# TopSheet.net
KiCad netlist of a schematic drawn in Altium Designer
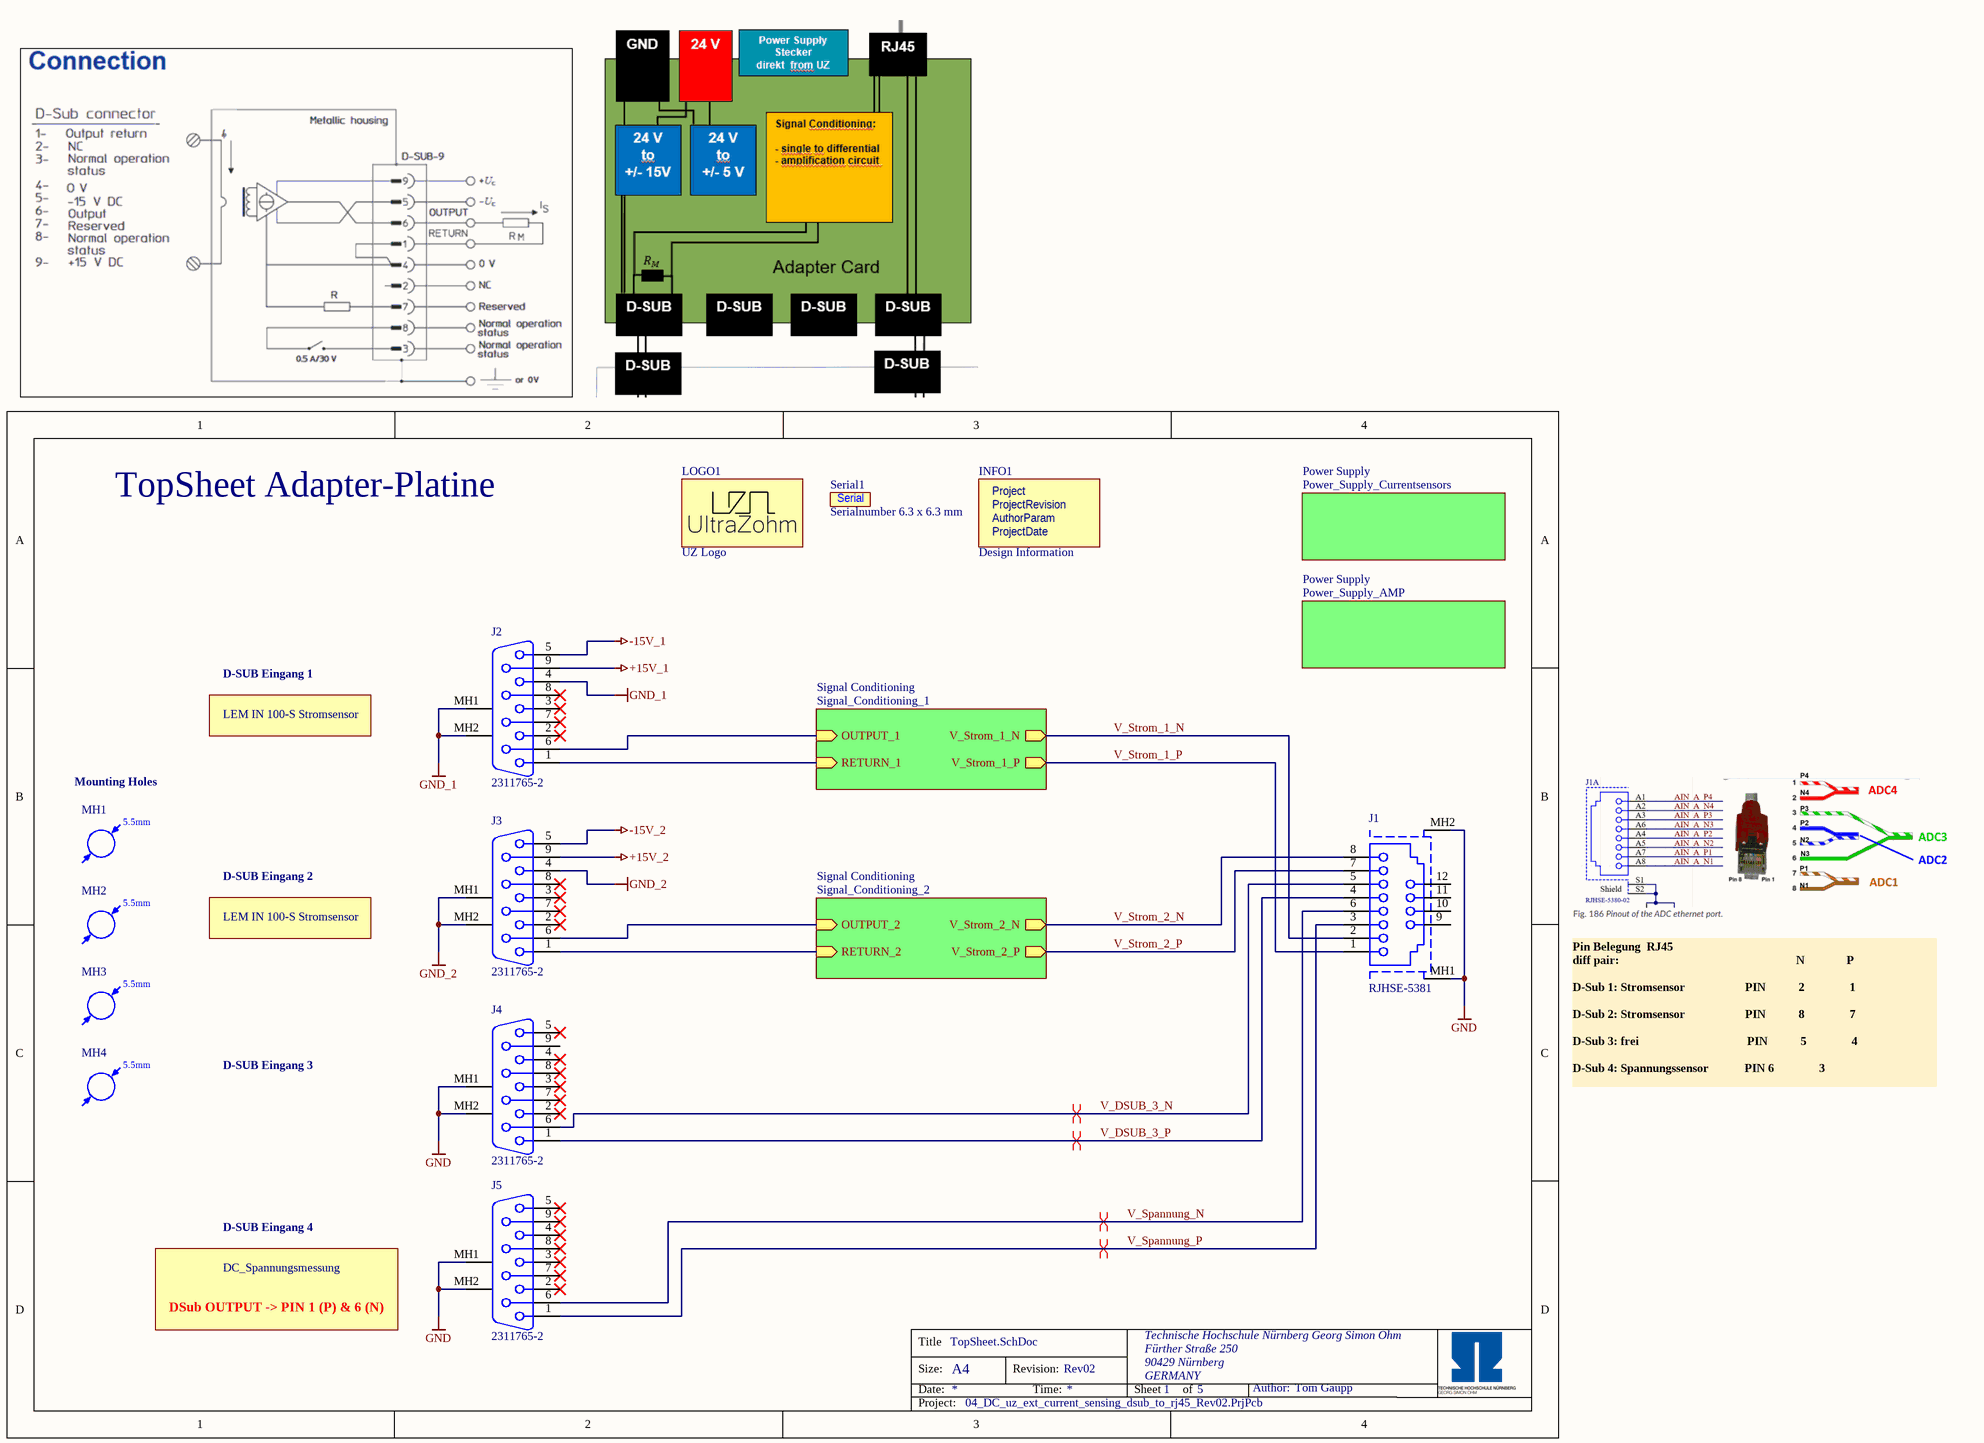
[diagram p0: TopSheet.SchDoc]

(export (version "E")
  (design (tool "Eeschema 10.0.6"))
  (components
    (comp (ref "INFO1")
      (value "Design Information")
      (footprint "Design_info")
      (description "Design InformationS")
      (fields (field (name "MANUFACTURER") "UltraZohm") (field (name "CREATED FROM") "MGremer"))
      (libsource (lib "user") (part "Design_info"))
    )
    (comp (ref "J1")
      (value "RJHSE-5381")
      (footprint "eigene_lib_alt:RJHSE-5381")
      (description "Connector Ethernet R/A RJ45 SHIELDED 8 CONT Y/G LEDS")
      (libsource (lib "eigene_lib_alt") (part "RJHSE-5381"))
    )
    (comp (ref "J2")
      (value "2311765-2")
      (footprint "eigene_lib_alt:23117652")
      (description "Connector D-Sub 9 Pin Female")
      (fields (field (name "MOUSER PART NUMBER") "571-2311765-2"))
      (libsource (lib "eigene_lib_alt") (part "2311765-2"))
    )
    (comp (ref "J3")
      (value "2311765-2")
      (footprint "eigene_lib_alt:23117652")
      (description "Connector D-Sub 9 Pin Female")
      (fields (field (name "MOUSER PART NUMBER") "571-2311765-2"))
      (libsource (lib "eigene_lib_alt") (part "2311765-2"))
    )
    (comp (ref "J4")
      (value "2311765-2")
      (footprint "eigene_lib_alt:23117652")
      (description "Connector D-Sub 9 Pin Female")
      (fields (field (name "MOUSER PART NUMBER") "571-2311765-2"))
      (libsource (lib "eigene_lib_alt") (part "2311765-2"))
    )
    (comp (ref "J5")
      (value "2311765-2")
      (footprint "eigene_lib_alt:23117652")
      (description "Connector D-Sub 9 Pin Female")
      (fields (field (name "MOUSER PART NUMBER") "571-2311765-2"))
      (libsource (lib "eigene_lib_alt") (part "2311765-2"))
    )
    (comp (ref "LOGO1")
      (value "UZ Logo")
      (footprint "UZ_Logo_small")
      (fields
        (field (name "MANUFACTURER PART NUMBER") "Logo small")
        (field (name "MANUFACTURER") "UltraZohm")
        (field (name "CREATED") "Jan2021_Liegmann")
        (field (name "CREATED FROM") "MGremer")
      )
      (libsource (lib "user") (part "UZ Logo"))
    )
    (comp (ref "MH1")
      (value "Mounting_Hole_M5")
      (footprint "Mounting_Hole_M5:Mounting Hole (M5)")
      (description "Mounting Hole")
      (libsource (lib "Mounting_Hole_M5") (part "Mounting_Hole_M5"))
    )
    (comp (ref "MH2")
      (value "Mounting_Hole_M5")
      (footprint "Mounting_Hole_M5:Mounting Hole (M5)")
      (description "Mounting Hole")
      (libsource (lib "Mounting_Hole_M5") (part "Mounting_Hole_M5"))
    )
    (comp (ref "MH3")
      (value "Mounting_Hole_M5")
      (footprint "Mounting_Hole_M5:Mounting Hole (M5)")
      (description "Mounting Hole")
      (libsource (lib "Mounting_Hole_M5") (part "Mounting_Hole_M5"))
    )
    (comp (ref "MH4")
      (value "Mounting_Hole_M5")
      (footprint "Mounting_Hole_M5:Mounting Hole (M5)")
      (description "Mounting Hole")
      (libsource (lib "Mounting_Hole_M5") (part "Mounting_Hole_M5"))
    )
    (comp (ref "Serial1")
      (value "Serialnumber 6.3 x 6.3 mm")
      (footprint "SERIAL_6.3X6.3MM")
      (description "Serial Number")
      (fields
        (field (name "MANUFACTURER") "UltraZohm")
        (field (name "CREATED") "2018_09_18_AGeiger")
        (field (name "CREATED FROM") "MGremer")
      )
      (libsource (lib "user") (part "SerialNumber"))
    )
  )
  (nets
    (net (code "1") (name "+15V_1") (class "Default")
      (node (ref "J2") (pin "9") (pinfunction "9_9") (pintype "passive"))
    )
    (net (code "2") (name "+15V_2") (class "Default")
      (node (ref "J3") (pin "9") (pinfunction "9_9") (pintype "passive"))
    )
    (net (code "3") (name "-15V_1") (class "Default")
      (node (ref "J2") (pin "5") (pinfunction "5_5") (pintype "passive"))
    )
    (net (code "4") (name "-15V_2") (class "Default")
      (node (ref "J3") (pin "5") (pinfunction "5_5") (pintype "passive"))
    )
    (net (code "5") (name "/OUTPUT_1") (class "Default")
      (node (ref "J2") (pin "6") (pinfunction "6_6") (pintype "passive"))
    )
    (net (code "6") (name "/OUTPUT_2") (class "Default")
      (node (ref "J3") (pin "6") (pinfunction "6_6") (pintype "passive"))
    )
    (net (code "7") (name "/RETURN_1") (class "Default")
      (node (ref "J2") (pin "1") (pinfunction "1_1") (pintype "passive"))
    )
    (net (code "8") (name "/RETURN_2") (class "Default")
      (node (ref "J3") (pin "1") (pinfunction "1_1") (pintype "passive"))
    )
    (net (code "9") (name "/V_DSUB_3_N") (class "Default")
      (node (ref "J1") (pin "5") (pinfunction "5_5") (pintype "passive"))
      (node (ref "J4") (pin "6") (pinfunction "6_6") (pintype "passive"))
    )
    (net (code "10") (name "/V_DSUB_3_P") (class "Default")
      (node (ref "J1") (pin "4") (pinfunction "4_4") (pintype "passive"))
      (node (ref "J4") (pin "1") (pinfunction "1_1") (pintype "passive"))
    )
    (net (code "11") (name "/V_Spannung_N") (class "Default")
      (node (ref "J1") (pin "6") (pinfunction "6_6") (pintype "passive"))
      (node (ref "J5") (pin "6") (pinfunction "6_6") (pintype "passive"))
    )
    (net (code "12") (name "/V_Spannung_P") (class "Default")
      (node (ref "J1") (pin "3") (pinfunction "3_3") (pintype "passive"))
      (node (ref "J5") (pin "1") (pinfunction "1_1") (pintype "passive"))
    )
    (net (code "13") (name "/V_Strom_1_N") (class "Default")
      (node (ref "J1") (pin "2") (pinfunction "2_2") (pintype "passive"))
    )
    (net (code "14") (name "/V_Strom_1_P") (class "Default")
      (node (ref "J1") (pin "1") (pinfunction "1_1") (pintype "passive"))
    )
    (net (code "15") (name "/V_Strom_2_N") (class "Default")
      (node (ref "J1") (pin "8") (pinfunction "8_8") (pintype "passive"))
    )
    (net (code "16") (name "/V_Strom_2_P") (class "Default")
      (node (ref "J1") (pin "7") (pinfunction "7_7") (pintype "passive"))
    )
    (net (code "17") (name "GND") (class "Default")
      (node (ref "J1") (pin "MH1") (pinfunction "Shell_MH1") (pintype "passive"))
      (node (ref "J1") (pin "MH2") (pinfunction "Shell_MH2") (pintype "passive"))
      (node (ref "J4") (pin "MH1") (pinfunction "MH1_MH1") (pintype "passive"))
      (node (ref "J4") (pin "MH2") (pinfunction "MH2_MH2") (pintype "passive"))
      (node (ref "J5") (pin "MH1") (pinfunction "MH1_MH1") (pintype "passive"))
      (node (ref "J5") (pin "MH2") (pinfunction "MH2_MH2") (pintype "passive"))
    )
    (net (code "18") (name "GND_1") (class "Default")
      (node (ref "J2") (pin "4") (pinfunction "4_4") (pintype "passive"))
      (node (ref "J2") (pin "MH1") (pinfunction "MH1_MH1") (pintype "passive"))
      (node (ref "J2") (pin "MH2") (pinfunction "MH2_MH2") (pintype "passive"))
    )
    (net (code "19") (name "GND_2") (class "Default")
      (node (ref "J3") (pin "4") (pinfunction "4_4") (pintype "passive"))
      (node (ref "J3") (pin "MH1") (pinfunction "MH1_MH1") (pintype "passive"))
      (node (ref "J3") (pin "MH2") (pinfunction "MH2_MH2") (pintype "passive"))
    )
    (net (code "20") (name "unconnected-(J1-8-Pad9)") (class "Default")
      (node (ref "J1") (pin "9") (pinfunction "8_9") (pintype "passive"))
    )
    (net (code "21") (name "unconnected-(J1-8-Pad10)") (class "Default")
      (node (ref "J1") (pin "10") (pinfunction "8_10") (pintype "passive"))
    )
    (net (code "22") (name "unconnected-(J1-8-Pad11)") (class "Default")
      (node (ref "J1") (pin "11") (pinfunction "8_11") (pintype "passive"))
    )
    (net (code "23") (name "unconnected-(J1-8-Pad12)") (class "Default")
      (node (ref "J1") (pin "12") (pinfunction "8_12") (pintype "passive"))
    )
    (net (code "24") (name "unconnected-(J2-Pad2)") (class "Default")
      (node (ref "J2") (pin "2") (pinfunction "2_2") (pintype "passive+no_connect"))
    )
    (net (code "25") (name "unconnected-(J2-Pad3)") (class "Default")
      (node (ref "J2") (pin "3") (pinfunction "3_3") (pintype "passive+no_connect"))
    )
    (net (code "26") (name "unconnected-(J2-Pad7)") (class "Default")
      (node (ref "J2") (pin "7") (pinfunction "7_7") (pintype "passive+no_connect"))
    )
    (net (code "27") (name "unconnected-(J2-Pad8)") (class "Default")
      (node (ref "J2") (pin "8") (pinfunction "8_8") (pintype "passive+no_connect"))
    )
    (net (code "28") (name "unconnected-(J3-Pad2)") (class "Default")
      (node (ref "J3") (pin "2") (pinfunction "2_2") (pintype "passive+no_connect"))
    )
    (net (code "29") (name "unconnected-(J3-Pad3)") (class "Default")
      (node (ref "J3") (pin "3") (pinfunction "3_3") (pintype "passive+no_connect"))
    )
    (net (code "30") (name "unconnected-(J3-Pad7)") (class "Default")
      (node (ref "J3") (pin "7") (pinfunction "7_7") (pintype "passive+no_connect"))
    )
    (net (code "31") (name "unconnected-(J3-Pad8)") (class "Default")
      (node (ref "J3") (pin "8") (pinfunction "8_8") (pintype "passive+no_connect"))
    )
    (net (code "32") (name "unconnected-(J4-Pad2)") (class "Default")
      (node (ref "J4") (pin "2") (pinfunction "2_2") (pintype "passive+no_connect"))
    )
    (net (code "33") (name "unconnected-(J4-Pad3)") (class "Default")
      (node (ref "J4") (pin "3") (pinfunction "3_3") (pintype "passive+no_connect"))
    )
    (net (code "34") (name "unconnected-(J4-Pad4)") (class "Default")
      (node (ref "J4") (pin "4") (pinfunction "4_4") (pintype "passive+no_connect"))
    )
    (net (code "35") (name "unconnected-(J4-Pad5)") (class "Default")
      (node (ref "J4") (pin "5") (pinfunction "5_5") (pintype "passive+no_connect"))
    )
    (net (code "36") (name "unconnected-(J4-Pad7)") (class "Default")
      (node (ref "J4") (pin "7") (pinfunction "7_7") (pintype "passive+no_connect"))
    )
    (net (code "37") (name "unconnected-(J4-Pad8)") (class "Default")
      (node (ref "J4") (pin "8") (pinfunction "8_8") (pintype "passive+no_connect"))
    )
    (net (code "38") (name "unconnected-(J4-Pad9)") (class "Default")
      (node (ref "J4") (pin "9") (pinfunction "9_9") (pintype "passive"))
    )
    (net (code "39") (name "unconnected-(J5-Pad2)") (class "Default")
      (node (ref "J5") (pin "2") (pinfunction "2_2") (pintype "passive+no_connect"))
    )
    (net (code "40") (name "unconnected-(J5-Pad3)") (class "Default")
      (node (ref "J5") (pin "3") (pinfunction "3_3") (pintype "passive+no_connect"))
    )
    (net (code "41") (name "unconnected-(J5-Pad4)") (class "Default")
      (node (ref "J5") (pin "4") (pinfunction "4_4") (pintype "passive+no_connect"))
    )
    (net (code "42") (name "unconnected-(J5-Pad5)") (class "Default")
      (node (ref "J5") (pin "5") (pinfunction "5_5") (pintype "passive+no_connect"))
    )
    (net (code "43") (name "unconnected-(J5-Pad7)") (class "Default")
      (node (ref "J5") (pin "7") (pinfunction "7_7") (pintype "passive+no_connect"))
    )
    (net (code "44") (name "unconnected-(J5-Pad8)") (class "Default")
      (node (ref "J5") (pin "8") (pinfunction "8_8") (pintype "passive+no_connect"))
    )
    (net (code "45") (name "unconnected-(J5-Pad9)") (class "Default")
      (node (ref "J5") (pin "9") (pinfunction "9_9") (pintype "passive+no_connect"))
    )
  )
)
